# Volant5_LEDdriver.net
KiCad netlist of a schematic drawn in Altium Designer
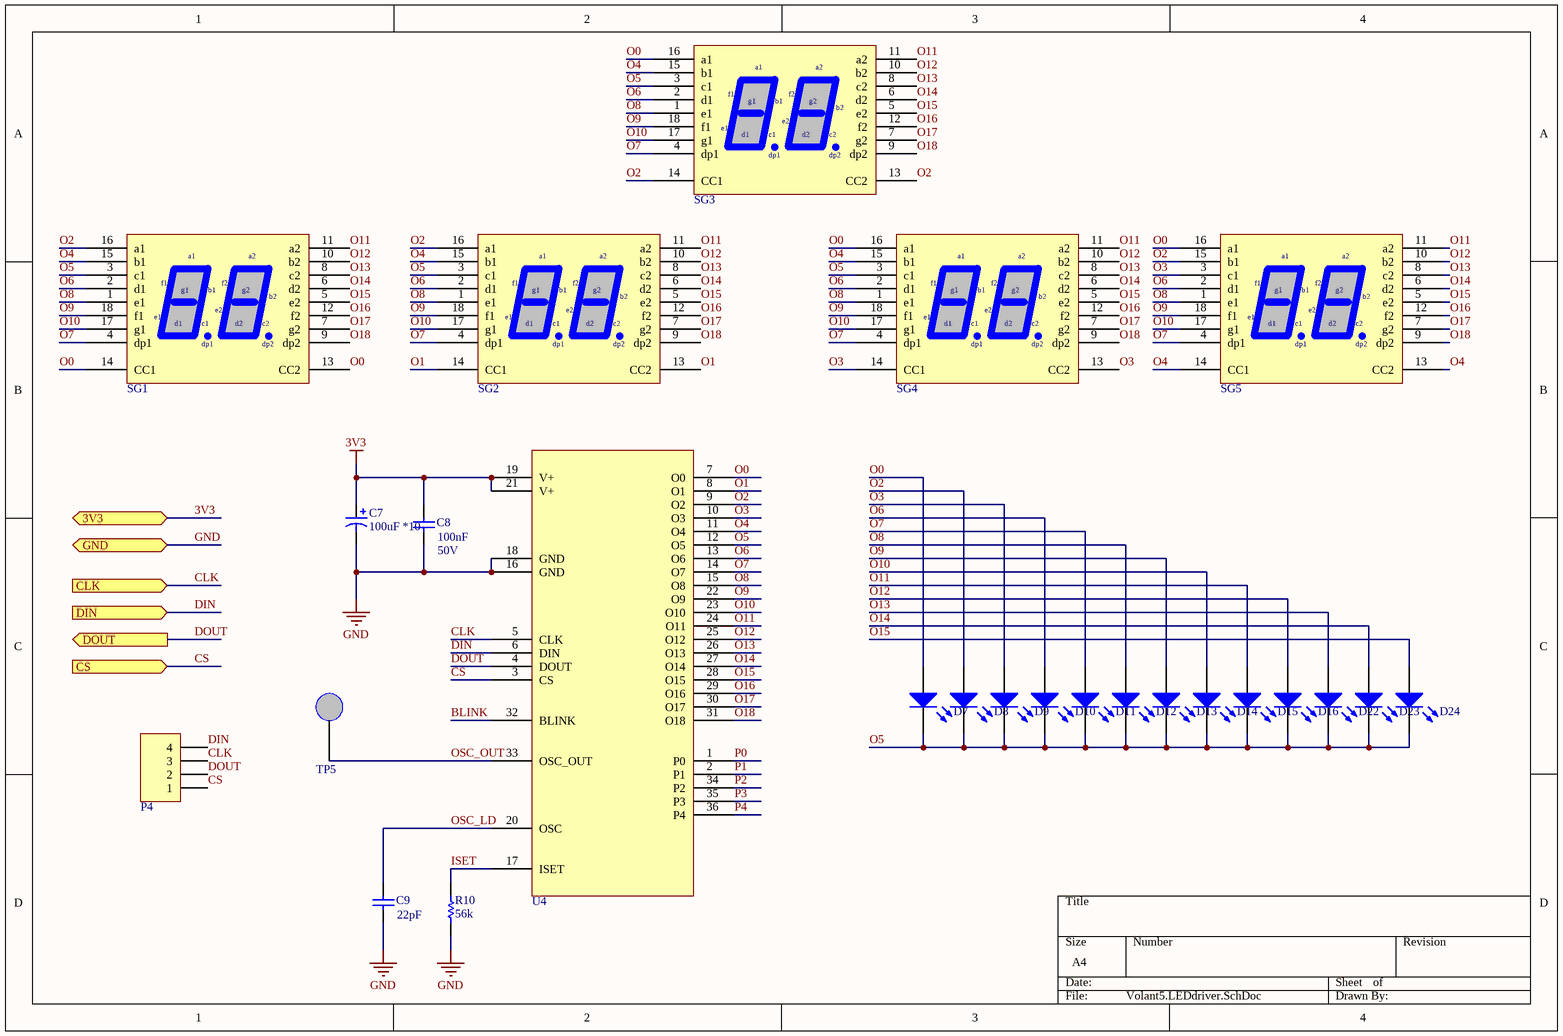
[diagram p0: Volant5.LEDdriver.SchDoc]

(export (version "E")
  (design (tool "Eeschema 10.0.6"))
  (components
    (comp (ref "C7")
      (value "100uF *10")
      (footprint "CS-POL-6.3X4.2")
      (fields
        (field (name "TOLERANCE") "10%")
        (field (name "VOLTAGE") "VOLTAGE")
        (field (name "Comment") "CS - CAPACITOR ELECTROLYTIC")
      )
      (libsource (lib "CHINOOK_LIBRARY") (part "CS - CAPACITOR ELECTROLYTIC"))
    )
    (comp (ref "C8")
      (value "100nF")
      (footprint "CS-0603")
      (fields
        (field (name "TOLERANCE") "10%")
        (field (name "VOLTAGE") "50V")
        (field (name "Comment") "CS - CAPACITOR")
      )
      (libsource (lib "CHINOOK_LIBRARY") (part "CS - CAPACITOR"))
    )
    (comp (ref "C9")
      (value "22pF")
      (footprint "CS-0603")
      (fields (field (name "TOLERANCE") "10%") (field (name "Comment") "CS - CAPACITOR"))
      (libsource (lib "CHINOOK_LIBRARY") (part "CS - CAPACITOR"))
    )
    (comp (ref "D7")
      (value "LED - NORMAL LED")
      (footprint "LED-1206 BLUE")
      (libsource (lib "CHINOOK-FOOTPRINT") (part "LED - NORMAL LED"))
    )
    (comp (ref "D8")
      (value "LED - NORMAL LED")
      (footprint "LED-1206 BLUE")
      (libsource (lib "CHINOOK-FOOTPRINT") (part "LED - NORMAL LED"))
    )
    (comp (ref "D9")
      (value "LED - NORMAL LED")
      (footprint "LED-1206 BLUE")
      (libsource (lib "CHINOOK-FOOTPRINT") (part "LED - NORMAL LED"))
    )
    (comp (ref "D10")
      (value "LED - NORMAL LED")
      (footprint "LED-1206 BLUE")
      (libsource (lib "CHINOOK-FOOTPRINT") (part "LED - NORMAL LED"))
    )
    (comp (ref "D11")
      (value "LED - NORMAL LED")
      (footprint "LED-1206 BLUE")
      (libsource (lib "CHINOOK-FOOTPRINT") (part "LED - NORMAL LED"))
    )
    (comp (ref "D12")
      (value "LED - NORMAL LED")
      (footprint "LED-1206 BLUE")
      (libsource (lib "CHINOOK-FOOTPRINT") (part "LED - NORMAL LED"))
    )
    (comp (ref "D13")
      (value "LED - NORMAL LED")
      (footprint "LED-1206 BLUE")
      (libsource (lib "CHINOOK-FOOTPRINT") (part "LED - NORMAL LED"))
    )
    (comp (ref "D14")
      (value "LED - NORMAL LED")
      (footprint "LED-1206 BLUE")
      (libsource (lib "CHINOOK-FOOTPRINT") (part "LED - NORMAL LED"))
    )
    (comp (ref "D15")
      (value "LED - NORMAL LED")
      (footprint "LED-1206 BLUE")
      (libsource (lib "CHINOOK-FOOTPRINT") (part "LED - NORMAL LED"))
    )
    (comp (ref "D16")
      (value "LED - NORMAL LED")
      (footprint "LED-1206 BLUE")
      (libsource (lib "CHINOOK-FOOTPRINT") (part "LED - NORMAL LED"))
    )
    (comp (ref "D22")
      (value "LED - NORMAL LED")
      (footprint "LED-1206 BLUE")
      (libsource (lib "CHINOOK-FOOTPRINT") (part "LED - NORMAL LED"))
    )
    (comp (ref "D23")
      (value "LED - NORMAL LED")
      (footprint "LED-1206 BLUE")
      (libsource (lib "CHINOOK-FOOTPRINT") (part "LED - NORMAL LED"))
    )
    (comp (ref "D24")
      (value "LED - NORMAL LED")
      (footprint "LED-1206 BLUE")
      (libsource (lib "CHINOOK-FOOTPRINT") (part "LED - NORMAL LED"))
    )
    (comp (ref "P4")
      (value "CON - HEADER 1X4")
      (footprint "CON-HEADER-1X4")
      (description "100mil header 1 row 4pins")
      (libsource (lib "CHINOOK_LIBRARY") (part "CON - HEADER 1X4"))
    )
    (comp (ref "R10")
      (value "56k")
      (footprint "RS-0603")
      (fields
        (field (name "TOLERANCE") "RES TOL")
        (field (name "POWER") "RES POWER")
        (field (name "Comment") "RS - RESISTOR")
      )
      (libsource (lib "CHINOOK_LIBRARY") (part "RS - RESISTOR"))
    )
    (comp (ref "SG1")
      (value "LB-602VK2")
      (footprint "DISP-DUAL 7SEG 18 pin")
      (description "DUAL 7 SEG DISP HIGH BRIGHTNESS")
      (fields (field (name "MANUFACTURER") "ROHM"))
      (libsource (lib "CHINOOK_LIBRARY") (part "DISP - LB-602VK2"))
    )
    (comp (ref "SG2")
      (value "LB-602VK2")
      (footprint "DISP-DUAL 7SEG 18 pin")
      (description "DUAL 7 SEG DISP HIGH BRIGHTNESS")
      (fields (field (name "MANUFACTURER") "ROHM"))
      (libsource (lib "CHINOOK_LIBRARY") (part "DISP - LB-602VK2"))
    )
    (comp (ref "SG3")
      (value "LB-602VK2")
      (footprint "DISP-DUAL 7SEG 18 pin")
      (description "DUAL 7 SEG DISP HIGH BRIGHTNESS")
      (fields (field (name "MANUFACTURER") "ROHM"))
      (libsource (lib "CHINOOK_LIBRARY") (part "DISP - LB-602VK2"))
    )
    (comp (ref "SG4")
      (value "LB-602VK2")
      (footprint "DISP-DUAL 7SEG 18 pin")
      (description "DUAL 7 SEG DISP HIGH BRIGHTNESS")
      (fields (field (name "MANUFACTURER") "ROHM"))
      (libsource (lib "CHINOOK_LIBRARY") (part "DISP - LB-602VK2"))
    )
    (comp (ref "SG5")
      (value "LB-602VK2")
      (footprint "DISP-DUAL 7SEG 18 pin")
      (description "DUAL 7 SEG DISP HIGH BRIGHTNESS")
      (fields (field (name "MANUFACTURER") "ROHM"))
      (libsource (lib "CHINOOK_LIBRARY") (part "DISP - LB-602VK2"))
    )
    (comp (ref "TP5")
      (value "OSC LED")
      (footprint "TP - VERTICAL")
      (libsource (lib "CHINOOK_LIBRARY") (part "TP - Test point vertical"))
    )
    (comp (ref "U4")
      (value "MAX6954AAX")
      (footprint "IC-SSOP-36")
      (description "DRIVE 8 DIGIT 7SEG")
      (fields (field (name "MANUFACTURER") "Maxim Integrated"))
      (libsource (lib "CHINOOK-FOOTPRINT") (part "IC - MAX6954"))
    )
  )
  (nets
    (net (code "1") (name "/BLINK") (class "Default")
      (node (ref "U4") (pin "32") (pinfunction "BLINK_32") (pintype "passive"))
    )
    (net (code "2") (name "/CLK") (class "Default")
      (node (ref "P4") (pin "3") (pinfunction "3_3") (pintype "passive"))
      (node (ref "U4") (pin "5") (pinfunction "CLK_5") (pintype "passive"))
    )
    (net (code "3") (name "/CS") (class "Default")
      (node (ref "P4") (pin "1") (pinfunction "1_1") (pintype "passive"))
      (node (ref "U4") (pin "3") (pinfunction "CS_3") (pintype "passive"))
    )
    (net (code "4") (name "/DIN") (class "Default")
      (node (ref "P4") (pin "4") (pinfunction "4_4") (pintype "passive"))
      (node (ref "U4") (pin "6") (pinfunction "DIN_6") (pintype "passive"))
    )
    (net (code "5") (name "/DOUT") (class "Default")
      (node (ref "P4") (pin "2") (pinfunction "2_2") (pintype "passive"))
      (node (ref "U4") (pin "4") (pinfunction "DOUT_4") (pintype "passive"))
    )
    (net (code "6") (name "/ISET") (class "Default")
      (node (ref "R10") (pin "2") (pinfunction "2_2") (pintype "passive"))
      (node (ref "U4") (pin "17") (pinfunction "ISET_17") (pintype "passive"))
    )
    (net (code "7") (name "/O0") (class "Default")
      (node (ref "D7") (pin "A") (pinfunction "A_A") (pintype "passive"))
      (node (ref "SG1") (pin "13") (pinfunction "CC2_13") (pintype "passive"))
      (node (ref "SG1") (pin "14") (pinfunction "CC1_14") (pintype "passive"))
      (node (ref "SG3") (pin "16") (pinfunction "a1_16") (pintype "passive"))
      (node (ref "SG4") (pin "16") (pinfunction "a1_16") (pintype "passive"))
      (node (ref "SG5") (pin "16") (pinfunction "a1_16") (pintype "passive"))
      (node (ref "U4") (pin "7") (pinfunction "O0_7") (pintype "passive"))
    )
    (net (code "8") (name "/O1") (class "Default")
      (node (ref "SG2") (pin "13") (pinfunction "CC2_13") (pintype "passive"))
      (node (ref "SG2") (pin "14") (pinfunction "CC1_14") (pintype "passive"))
      (node (ref "U4") (pin "8") (pinfunction "O1_8") (pintype "passive"))
    )
    (net (code "9") (name "/O2") (class "Default")
      (node (ref "D8") (pin "A") (pinfunction "A_A") (pintype "passive"))
      (node (ref "SG1") (pin "16") (pinfunction "a1_16") (pintype "passive"))
      (node (ref "SG2") (pin "16") (pinfunction "a1_16") (pintype "passive"))
      (node (ref "SG3") (pin "13") (pinfunction "CC2_13") (pintype "passive"))
      (node (ref "SG3") (pin "14") (pinfunction "CC1_14") (pintype "passive"))
      (node (ref "SG5") (pin "15") (pinfunction "b1_15") (pintype "passive"))
      (node (ref "U4") (pin "9") (pinfunction "O2_9") (pintype "passive"))
    )
    (net (code "10") (name "/O3") (class "Default")
      (node (ref "D9") (pin "A") (pinfunction "A_A") (pintype "passive"))
      (node (ref "SG4") (pin "13") (pinfunction "CC2_13") (pintype "passive"))
      (node (ref "SG4") (pin "14") (pinfunction "CC1_14") (pintype "passive"))
      (node (ref "SG5") (pin "3") (pinfunction "c1_3") (pintype "passive"))
      (node (ref "U4") (pin "10") (pinfunction "O3_10") (pintype "passive"))
    )
    (net (code "11") (name "/O4") (class "Default")
      (node (ref "SG1") (pin "15") (pinfunction "b1_15") (pintype "passive"))
      (node (ref "SG2") (pin "15") (pinfunction "b1_15") (pintype "passive"))
      (node (ref "SG3") (pin "15") (pinfunction "b1_15") (pintype "passive"))
      (node (ref "SG4") (pin "15") (pinfunction "b1_15") (pintype "passive"))
      (node (ref "SG5") (pin "13") (pinfunction "CC2_13") (pintype "passive"))
      (node (ref "SG5") (pin "14") (pinfunction "CC1_14") (pintype "passive"))
      (node (ref "U4") (pin "11") (pinfunction "O4_11") (pintype "passive"))
    )
    (net (code "12") (name "/O5") (class "Default")
      (node (ref "D10") (pin "K") (pinfunction "K_K") (pintype "passive"))
      (node (ref "D11") (pin "K") (pinfunction "K_K") (pintype "passive"))
      (node (ref "D12") (pin "K") (pinfunction "K_K") (pintype "passive"))
      (node (ref "D13") (pin "K") (pinfunction "K_K") (pintype "passive"))
      (node (ref "D14") (pin "K") (pinfunction "K_K") (pintype "passive"))
      (node (ref "D15") (pin "K") (pinfunction "K_K") (pintype "passive"))
      (node (ref "D16") (pin "K") (pinfunction "K_K") (pintype "passive"))
      (node (ref "D22") (pin "K") (pinfunction "K_K") (pintype "passive"))
      (node (ref "D23") (pin "K") (pinfunction "K_K") (pintype "passive"))
      (node (ref "D24") (pin "K") (pinfunction "K_K") (pintype "passive"))
      (node (ref "D7") (pin "K") (pinfunction "K_K") (pintype "passive"))
      (node (ref "D8") (pin "K") (pinfunction "K_K") (pintype "passive"))
      (node (ref "D9") (pin "K") (pinfunction "K_K") (pintype "passive"))
      (node (ref "SG1") (pin "3") (pinfunction "c1_3") (pintype "passive"))
      (node (ref "SG2") (pin "3") (pinfunction "c1_3") (pintype "passive"))
      (node (ref "SG3") (pin "3") (pinfunction "c1_3") (pintype "passive"))
      (node (ref "SG4") (pin "3") (pinfunction "c1_3") (pintype "passive"))
      (node (ref "U4") (pin "12") (pinfunction "O5_12") (pintype "passive"))
    )
    (net (code "13") (name "/O6") (class "Default")
      (node (ref "D10") (pin "A") (pinfunction "A_A") (pintype "passive"))
      (node (ref "SG1") (pin "2") (pinfunction "d1_2") (pintype "passive"))
      (node (ref "SG2") (pin "2") (pinfunction "d1_2") (pintype "passive"))
      (node (ref "SG3") (pin "2") (pinfunction "d1_2") (pintype "passive"))
      (node (ref "SG4") (pin "2") (pinfunction "d1_2") (pintype "passive"))
      (node (ref "SG5") (pin "2") (pinfunction "d1_2") (pintype "passive"))
      (node (ref "U4") (pin "13") (pinfunction "O6_13") (pintype "passive"))
    )
    (net (code "14") (name "/O7") (class "Default")
      (node (ref "D11") (pin "A") (pinfunction "A_A") (pintype "passive"))
      (node (ref "SG1") (pin "4") (pinfunction "dp1_4") (pintype "passive"))
      (node (ref "SG2") (pin "4") (pinfunction "dp1_4") (pintype "passive"))
      (node (ref "SG3") (pin "4") (pinfunction "dp1_4") (pintype "passive"))
      (node (ref "SG4") (pin "4") (pinfunction "dp1_4") (pintype "passive"))
      (node (ref "SG5") (pin "4") (pinfunction "dp1_4") (pintype "passive"))
      (node (ref "U4") (pin "14") (pinfunction "O7_14") (pintype "passive"))
    )
    (net (code "15") (name "/O8") (class "Default")
      (node (ref "D12") (pin "A") (pinfunction "A_A") (pintype "passive"))
      (node (ref "SG1") (pin "1") (pinfunction "e1_1") (pintype "passive"))
      (node (ref "SG2") (pin "1") (pinfunction "e1_1") (pintype "passive"))
      (node (ref "SG3") (pin "1") (pinfunction "e1_1") (pintype "passive"))
      (node (ref "SG4") (pin "1") (pinfunction "e1_1") (pintype "passive"))
      (node (ref "SG5") (pin "1") (pinfunction "e1_1") (pintype "passive"))
      (node (ref "U4") (pin "15") (pinfunction "O8_15") (pintype "passive"))
    )
    (net (code "16") (name "/O9") (class "Default")
      (node (ref "D13") (pin "A") (pinfunction "A_A") (pintype "passive"))
      (node (ref "SG1") (pin "18") (pinfunction "f1_18") (pintype "passive"))
      (node (ref "SG2") (pin "18") (pinfunction "f1_18") (pintype "passive"))
      (node (ref "SG3") (pin "18") (pinfunction "f1_18") (pintype "passive"))
      (node (ref "SG4") (pin "18") (pinfunction "f1_18") (pintype "passive"))
      (node (ref "SG5") (pin "18") (pinfunction "f1_18") (pintype "passive"))
      (node (ref "U4") (pin "22") (pinfunction "O9_22") (pintype "passive"))
    )
    (net (code "17") (name "/O10") (class "Default")
      (node (ref "D14") (pin "A") (pinfunction "A_A") (pintype "passive"))
      (node (ref "SG1") (pin "17") (pinfunction "g1_17") (pintype "passive"))
      (node (ref "SG2") (pin "17") (pinfunction "g1_17") (pintype "passive"))
      (node (ref "SG3") (pin "17") (pinfunction "g1_17") (pintype "passive"))
      (node (ref "SG4") (pin "17") (pinfunction "g1_17") (pintype "passive"))
      (node (ref "SG5") (pin "17") (pinfunction "g1_17") (pintype "passive"))
      (node (ref "U4") (pin "23") (pinfunction "O10_23") (pintype "passive"))
    )
    (net (code "18") (name "/O11") (class "Default")
      (node (ref "D15") (pin "A") (pinfunction "A_A") (pintype "passive"))
      (node (ref "SG1") (pin "11") (pinfunction "a2_11") (pintype "passive"))
      (node (ref "SG2") (pin "11") (pinfunction "a2_11") (pintype "passive"))
      (node (ref "SG3") (pin "11") (pinfunction "a2_11") (pintype "passive"))
      (node (ref "SG4") (pin "11") (pinfunction "a2_11") (pintype "passive"))
      (node (ref "SG5") (pin "11") (pinfunction "a2_11") (pintype "passive"))
      (node (ref "U4") (pin "24") (pinfunction "O11_24") (pintype "passive"))
    )
    (net (code "19") (name "/O12") (class "Default")
      (node (ref "D16") (pin "A") (pinfunction "A_A") (pintype "passive"))
      (node (ref "SG1") (pin "10") (pinfunction "b2_10") (pintype "passive"))
      (node (ref "SG2") (pin "10") (pinfunction "b2_10") (pintype "passive"))
      (node (ref "SG3") (pin "10") (pinfunction "b2_10") (pintype "passive"))
      (node (ref "SG4") (pin "10") (pinfunction "b2_10") (pintype "passive"))
      (node (ref "SG5") (pin "10") (pinfunction "b2_10") (pintype "passive"))
      (node (ref "U4") (pin "25") (pinfunction "O12_25") (pintype "passive"))
    )
    (net (code "20") (name "/O13") (class "Default")
      (node (ref "D22") (pin "A") (pinfunction "A_A") (pintype "passive"))
      (node (ref "SG1") (pin "8") (pinfunction "c2_8") (pintype "passive"))
      (node (ref "SG2") (pin "8") (pinfunction "c2_8") (pintype "passive"))
      (node (ref "SG3") (pin "8") (pinfunction "c2_8") (pintype "passive"))
      (node (ref "SG4") (pin "8") (pinfunction "c2_8") (pintype "passive"))
      (node (ref "SG5") (pin "8") (pinfunction "c2_8") (pintype "passive"))
      (node (ref "U4") (pin "26") (pinfunction "O13_26") (pintype "passive"))
    )
    (net (code "21") (name "/O14") (class "Default")
      (node (ref "D23") (pin "A") (pinfunction "A_A") (pintype "passive"))
      (node (ref "SG1") (pin "6") (pinfunction "d2_6") (pintype "passive"))
      (node (ref "SG2") (pin "6") (pinfunction "d2_6") (pintype "passive"))
      (node (ref "SG3") (pin "6") (pinfunction "d2_6") (pintype "passive"))
      (node (ref "SG4") (pin "6") (pinfunction "d2_6") (pintype "passive"))
      (node (ref "SG5") (pin "6") (pinfunction "d2_6") (pintype "passive"))
      (node (ref "U4") (pin "27") (pinfunction "O14_27") (pintype "passive"))
    )
    (net (code "22") (name "/O15") (class "Default")
      (node (ref "D24") (pin "A") (pinfunction "A_A") (pintype "passive"))
      (node (ref "SG1") (pin "5") (pinfunction "e2_5") (pintype "passive"))
      (node (ref "SG2") (pin "5") (pinfunction "e2_5") (pintype "passive"))
      (node (ref "SG3") (pin "5") (pinfunction "e2_5") (pintype "passive"))
      (node (ref "SG4") (pin "5") (pinfunction "e2_5") (pintype "passive"))
      (node (ref "SG5") (pin "5") (pinfunction "e2_5") (pintype "passive"))
      (node (ref "U4") (pin "28") (pinfunction "O15_28") (pintype "passive"))
    )
    (net (code "23") (name "/O16") (class "Default")
      (node (ref "SG1") (pin "12") (pinfunction "f2_12") (pintype "passive"))
      (node (ref "SG2") (pin "12") (pinfunction "f2_12") (pintype "passive"))
      (node (ref "SG3") (pin "12") (pinfunction "f2_12") (pintype "passive"))
      (node (ref "SG4") (pin "12") (pinfunction "f2_12") (pintype "passive"))
      (node (ref "SG5") (pin "12") (pinfunction "f2_12") (pintype "passive"))
      (node (ref "U4") (pin "29") (pinfunction "O16_29") (pintype "passive"))
    )
    (net (code "24") (name "/O17") (class "Default")
      (node (ref "SG1") (pin "7") (pinfunction "g2_7") (pintype "passive"))
      (node (ref "SG2") (pin "7") (pinfunction "g2_7") (pintype "passive"))
      (node (ref "SG3") (pin "7") (pinfunction "g2_7") (pintype "passive"))
      (node (ref "SG4") (pin "7") (pinfunction "g2_7") (pintype "passive"))
      (node (ref "SG5") (pin "7") (pinfunction "g2_7") (pintype "passive"))
      (node (ref "U4") (pin "30") (pinfunction "O17_30") (pintype "passive"))
    )
    (net (code "25") (name "/O18") (class "Default")
      (node (ref "SG1") (pin "9") (pinfunction "dp2_9") (pintype "passive"))
      (node (ref "SG2") (pin "9") (pinfunction "dp2_9") (pintype "passive"))
      (node (ref "SG3") (pin "9") (pinfunction "dp2_9") (pintype "passive"))
      (node (ref "SG4") (pin "9") (pinfunction "dp2_9") (pintype "passive"))
      (node (ref "SG5") (pin "9") (pinfunction "dp2_9") (pintype "passive"))
      (node (ref "U4") (pin "31") (pinfunction "O18_31") (pintype "passive"))
    )
    (net (code "26") (name "/OSC_LD") (class "Default")
      (node (ref "C9") (pin "2") (pinfunction "2_2") (pintype "passive"))
      (node (ref "U4") (pin "20") (pinfunction "OSC_20") (pintype "passive"))
    )
    (net (code "27") (name "/OSC_OUT") (class "Default")
      (node (ref "TP5") (pin "1") (pinfunction "1_1") (pintype "passive"))
      (node (ref "U4") (pin "33") (pinfunction "OSC_OUT_33") (pintype "passive"))
    )
    (net (code "28") (name "/P0") (class "Default")
      (node (ref "U4") (pin "1") (pinfunction "P0_1") (pintype "passive"))
    )
    (net (code "29") (name "/P1") (class "Default")
      (node (ref "U4") (pin "2") (pinfunction "P1_2") (pintype "passive"))
    )
    (net (code "30") (name "/P2") (class "Default")
      (node (ref "U4") (pin "34") (pinfunction "P2_34") (pintype "passive"))
    )
    (net (code "31") (name "/P3") (class "Default")
      (node (ref "U4") (pin "35") (pinfunction "P3_35") (pintype "passive"))
    )
    (net (code "32") (name "/P4") (class "Default")
      (node (ref "U4") (pin "36") (pinfunction "P4_36") (pintype "passive"))
    )
    (net (code "33") (name "3V3") (class "Default")
      (node (ref "C7") (pin "1") (pinfunction "1_1") (pintype "passive"))
      (node (ref "C8") (pin "2") (pinfunction "2_2") (pintype "passive"))
      (node (ref "U4") (pin "19") (pinfunction "V+_19") (pintype "passive"))
      (node (ref "U4") (pin "21") (pinfunction "V+_21") (pintype "passive"))
    )
    (net (code "34") (name "GND") (class "Default")
      (node (ref "C7") (pin "2") (pinfunction "2_2") (pintype "passive"))
      (node (ref "C8") (pin "1") (pinfunction "1_1") (pintype "passive"))
      (node (ref "C9") (pin "1") (pinfunction "1_1") (pintype "passive"))
      (node (ref "R10") (pin "1") (pinfunction "1_1") (pintype "passive"))
      (node (ref "U4") (pin "16") (pinfunction "GND_16") (pintype "passive"))
      (node (ref "U4") (pin "18") (pinfunction "GND_18") (pintype "passive"))
    )
  )
)
